# 20_-CONNECT_CONNECTORS.net
KiCad netlist of a schematic drawn in Altium Designer
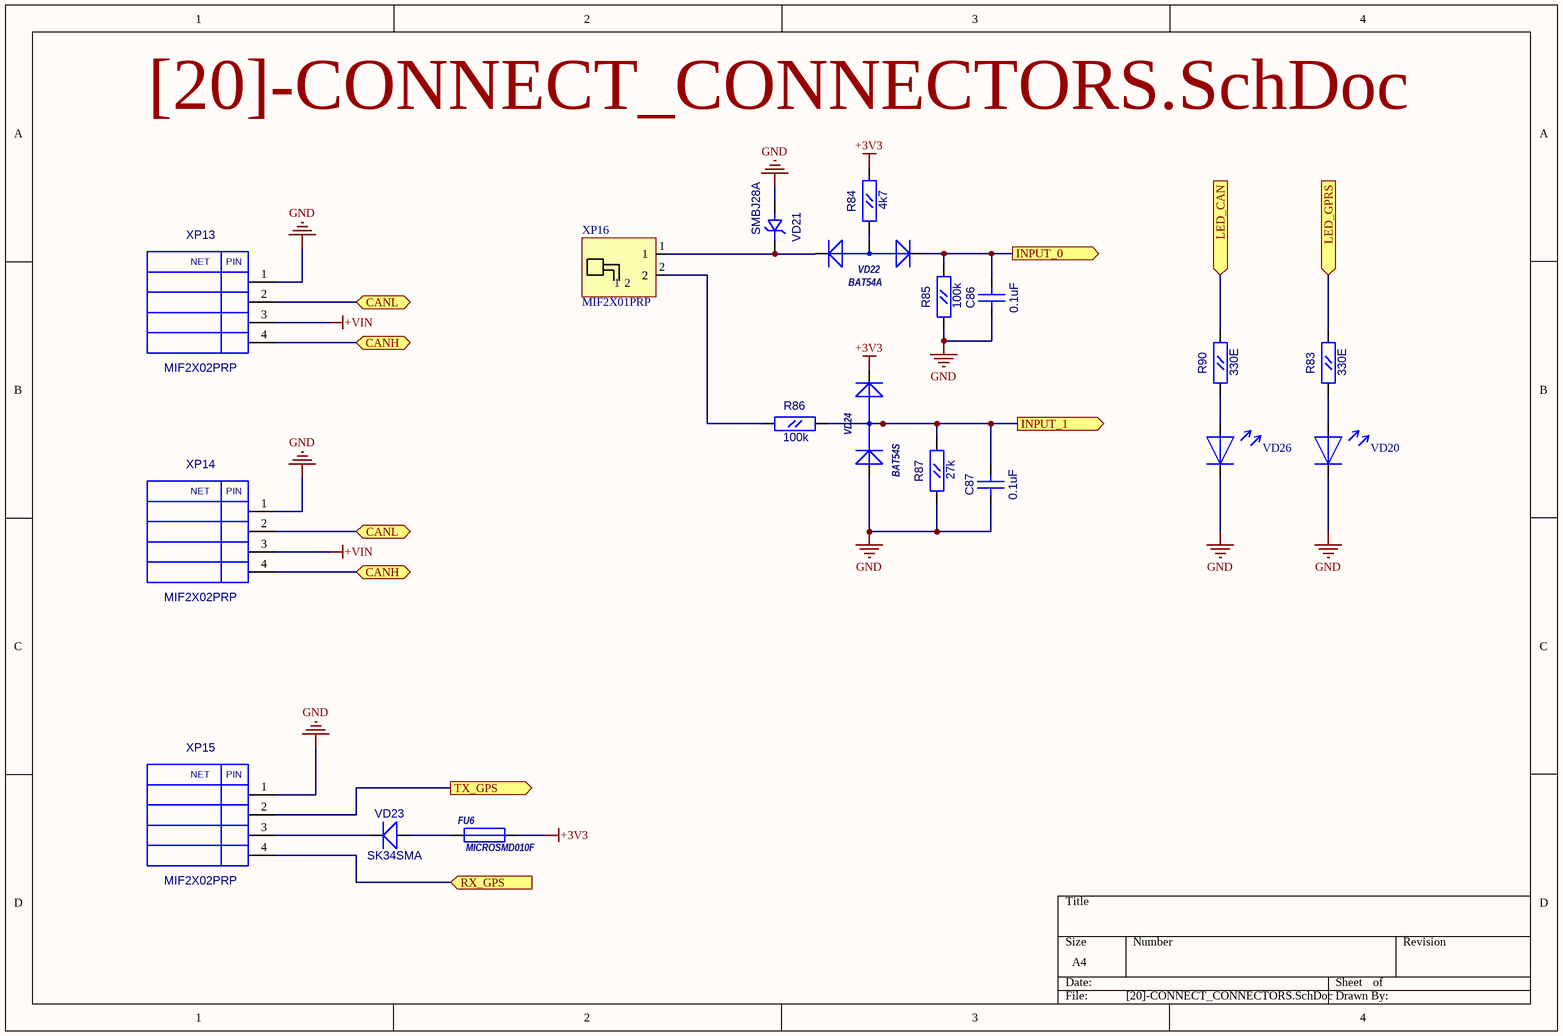
[diagram p0: [20]-CONNECT_CONNECTORS.SchDoc]

(export (version "E")
  (design (tool "Eeschema 10.0.6"))
  (components
    (comp (ref "C86")
      (value "0.1uF")
      (footprint "CC0603")
      (description "CC0603")
      (libsource (lib "fizik_lib") (part "CC0603"))
    )
    (comp (ref "C87")
      (value "0.1uF")
      (footprint "CC0603")
      (description "CC0603")
      (libsource (lib "gprs_modem_2") (part "CC0603"))
    )
    (comp (ref "FU6")
      (value "MICROSMD010F")
      (footprint "RC1210")
      (description "MICROSMD")
      (libsource (lib "fizik_lib") (part "MICROSMD"))
    )
    (comp (ref "R83")
      (value "330E")
      (footprint "RC0603")
      (description "RC0603")
      (libsource (lib "fizik_lib") (part "RC0603"))
    )
    (comp (ref "R84")
      (value "4k7")
      (footprint "RC0603")
      (description "RC0603")
      (libsource (lib "fizik_lib") (part "RC0603"))
    )
    (comp (ref "R85")
      (value "100k")
      (footprint "RC0603")
      (description "RC0603")
      (libsource (lib "fizik_lib") (part "RC0603"))
    )
    (comp (ref "R86")
      (value "100k")
      (footprint "RC0603")
      (description "RC0603")
      (libsource (lib "fizik_lib") (part "RC0603"))
    )
    (comp (ref "R87")
      (value "27k")
      (footprint "RC0603")
      (description "RC0603")
      (libsource (lib "fizik_lib") (part "RC0603"))
    )
    (comp (ref "R90")
      (value "330E")
      (footprint "RC0603")
      (description "RC0603")
      (libsource (lib "fizik_lib") (part "RC0603"))
    )
    (comp (ref "VD20")
      (value "LED_0805")
      (footprint "LED0805")
      (libsource (lib "fizik_lib") (part "LED_0805"))
    )
    (comp (ref "VD21")
      (value "SMBJ28A")
      (footprint "SMB")
      (description "SMBJ")
      (libsource (lib "fizik_lib") (part "SMBJ"))
    )
    (comp (ref "VD22")
      (value "BAT54A")
      (footprint "SOT-23(123)")
      (description "1.0 Ampere General Purpose Rectifier")
      (libsource (lib "fizik_lib") (part "BAT54A"))
    )
    (comp (ref "VD23")
      (value "SK34SMA")
      (footprint "SMA")
      (description "Schottky Rectifier")
      (libsource (lib "fizik_lib") (part "SK34SMA"))
    )
    (comp (ref "VD24")
      (value "BAT54S")
      (footprint "SOT-23(GSD)")
      (description "1.0 Ampere General Purpose Rectifier")
      (libsource (lib "fizik_lib") (part "BAT54S"))
    )
    (comp (ref "VD26")
      (value "LED_0805")
      (footprint "LED0805")
      (libsource (lib "fizik_lib") (part "LED_0805"))
    )
    (comp (ref "XP13")
      (value "MIF2X02PRP")
      (footprint "MIF2X02PRP")
      (libsource (lib "fizik_lib") (part "MIF2X02PRP"))
    )
    (comp (ref "XP14")
      (value "MIF2X02PRP")
      (footprint "MIF2X02PRP")
      (libsource (lib "fizik_lib") (part "MIF2X02PRP"))
    )
    (comp (ref "XP15")
      (value "MIF2X02PRP")
      (footprint "MIF2X02PRP")
      (libsource (lib "fizik_lib") (part "MIF2X02PRP"))
    )
    (comp (ref "XP16")
      (value "MIF2X01PRP")
      (footprint "MIF2x01PRP")
      (description "Molex connector 3.0mm pitch")
      (libsource (lib "fizik_lib") (part "MIF2X01PRP"))
    )
  )
  (nets
    (net (code "1") (name "+3V3") (class "Default")
      (node (ref "FU6") (pin "2") (pintype "passive"))
      (node (ref "R84") (pin "2") (pinfunction "B_2") (pintype "passive"))
      (node (ref "VD24") (pin "2") (pinfunction "K_2") (pintype "passive"))
    )
    (net (code "2") (name "+VIN") (class "Default")
      (node (ref "XP13") (pin "3") (pinfunction "3_3") (pintype "passive"))
      (node (ref "XP14") (pin "3") (pinfunction "3_3") (pintype "passive"))
    )
    (net (code "3") (name "/CANH") (class "Default")
      (node (ref "XP13") (pin "4") (pinfunction "4_4") (pintype "passive"))
      (node (ref "XP14") (pin "4") (pinfunction "4_4") (pintype "passive"))
    )
    (net (code "4") (name "/CANL") (class "Default")
      (node (ref "XP13") (pin "2") (pinfunction "2_2") (pintype "passive"))
      (node (ref "XP14") (pin "2") (pinfunction "2_2") (pintype "passive"))
    )
    (net (code "5") (name "/INPUT_0") (class "Default")
      (node (ref "C86") (pin "2") (pinfunction "B_2") (pintype "passive"))
      (node (ref "R85") (pin "2") (pinfunction "B_2") (pintype "passive"))
      (node (ref "VD22") (pin "2") (pinfunction "K_2") (pintype "passive"))
    )
    (net (code "6") (name "/INPUT_1") (class "Default")
      (node (ref "C87") (pin "2") (pinfunction "B_2") (pintype "passive"))
      (node (ref "R86") (pin "2") (pinfunction "B_2") (pintype "passive"))
      (node (ref "R87") (pin "2") (pinfunction "B_2") (pintype "passive"))
      (node (ref "VD24") (pin "3") (pinfunction "AK_3") (pintype "passive"))
    )
    (net (code "7") (name "/LED_CAN") (class "Default")
      (node (ref "R90") (pin "2") (pinfunction "B_2") (pintype "passive"))
    )
    (net (code "8") (name "/LED_GPRS") (class "Default")
      (node (ref "R83") (pin "2") (pinfunction "B_2") (pintype "passive"))
    )
    (net (code "9") (name "/RX_GPS") (class "Default")
      (node (ref "XP15") (pin "4") (pinfunction "4_4") (pintype "passive"))
    )
    (net (code "10") (name "/TX_GPS") (class "Default")
      (node (ref "XP15") (pin "2") (pinfunction "2_2") (pintype "passive"))
    )
    (net (code "11") (name "GND") (class "Default")
      (node (ref "C86") (pin "1") (pinfunction "A_1") (pintype "passive"))
      (node (ref "C87") (pin "1") (pinfunction "A_1") (pintype "passive"))
      (node (ref "R85") (pin "1") (pinfunction "A_1") (pintype "passive"))
      (node (ref "R87") (pin "1") (pinfunction "A_1") (pintype "passive"))
      (node (ref "VD20") (pin "2") (pintype "passive"))
      (node (ref "VD21") (pin "1") (pinfunction "A_1") (pintype "passive"))
      (node (ref "VD24") (pin "1") (pinfunction "A_1") (pintype "passive"))
      (node (ref "VD26") (pin "2") (pintype "passive"))
      (node (ref "XP13") (pin "1") (pinfunction "1_1") (pintype "passive"))
      (node (ref "XP14") (pin "1") (pinfunction "1_1") (pintype "passive"))
      (node (ref "XP15") (pin "1") (pinfunction "1_1") (pintype "passive"))
    )
    (net (code "12") (name "Net-(R83-A)") (class "Default")
      (node (ref "R83") (pin "1") (pinfunction "A_1") (pintype "passive"))
      (node (ref "VD20") (pin "1") (pintype "passive"))
    )
    (net (code "13") (name "Net-(R84-A)") (class "Default")
      (node (ref "R84") (pin "1") (pinfunction "A_1") (pintype "passive"))
      (node (ref "VD22") (pin "3") (pinfunction "A_3") (pintype "passive"))
    )
    (net (code "14") (name "Net-(R86-A)") (class "Default")
      (node (ref "R86") (pin "1") (pinfunction "A_1") (pintype "passive"))
      (node (ref "XP16") (pin "2") (pinfunction "2_2") (pintype "passive"))
    )
    (net (code "15") (name "Net-(R90-A)") (class "Default")
      (node (ref "R90") (pin "1") (pinfunction "A_1") (pintype "passive"))
      (node (ref "VD26") (pin "1") (pintype "passive"))
    )
    (net (code "16") (name "Net-(VD21-K)") (class "Default")
      (node (ref "VD21") (pin "2") (pinfunction "K_2") (pintype "passive"))
      (node (ref "VD22") (pin "1") (pinfunction "K_1") (pintype "passive"))
      (node (ref "XP16") (pin "1") (pinfunction "1_1") (pintype "passive"))
    )
    (net (code "17") (name "Net-(VD23-A)") (class "Default")
      (node (ref "FU6") (pin "1") (pintype "passive"))
      (node (ref "VD23") (pin "1") (pinfunction "A_1") (pintype "passive"))
    )
    (net (code "18") (name "Net-(VD23-K)") (class "Default")
      (node (ref "VD23") (pin "2") (pinfunction "K_2") (pintype "passive"))
      (node (ref "XP15") (pin "3") (pinfunction "3_3") (pintype "passive"))
    )
  )
)
